# Flyback_Develop.net
KiCad netlist of a schematic drawn in EAGLE
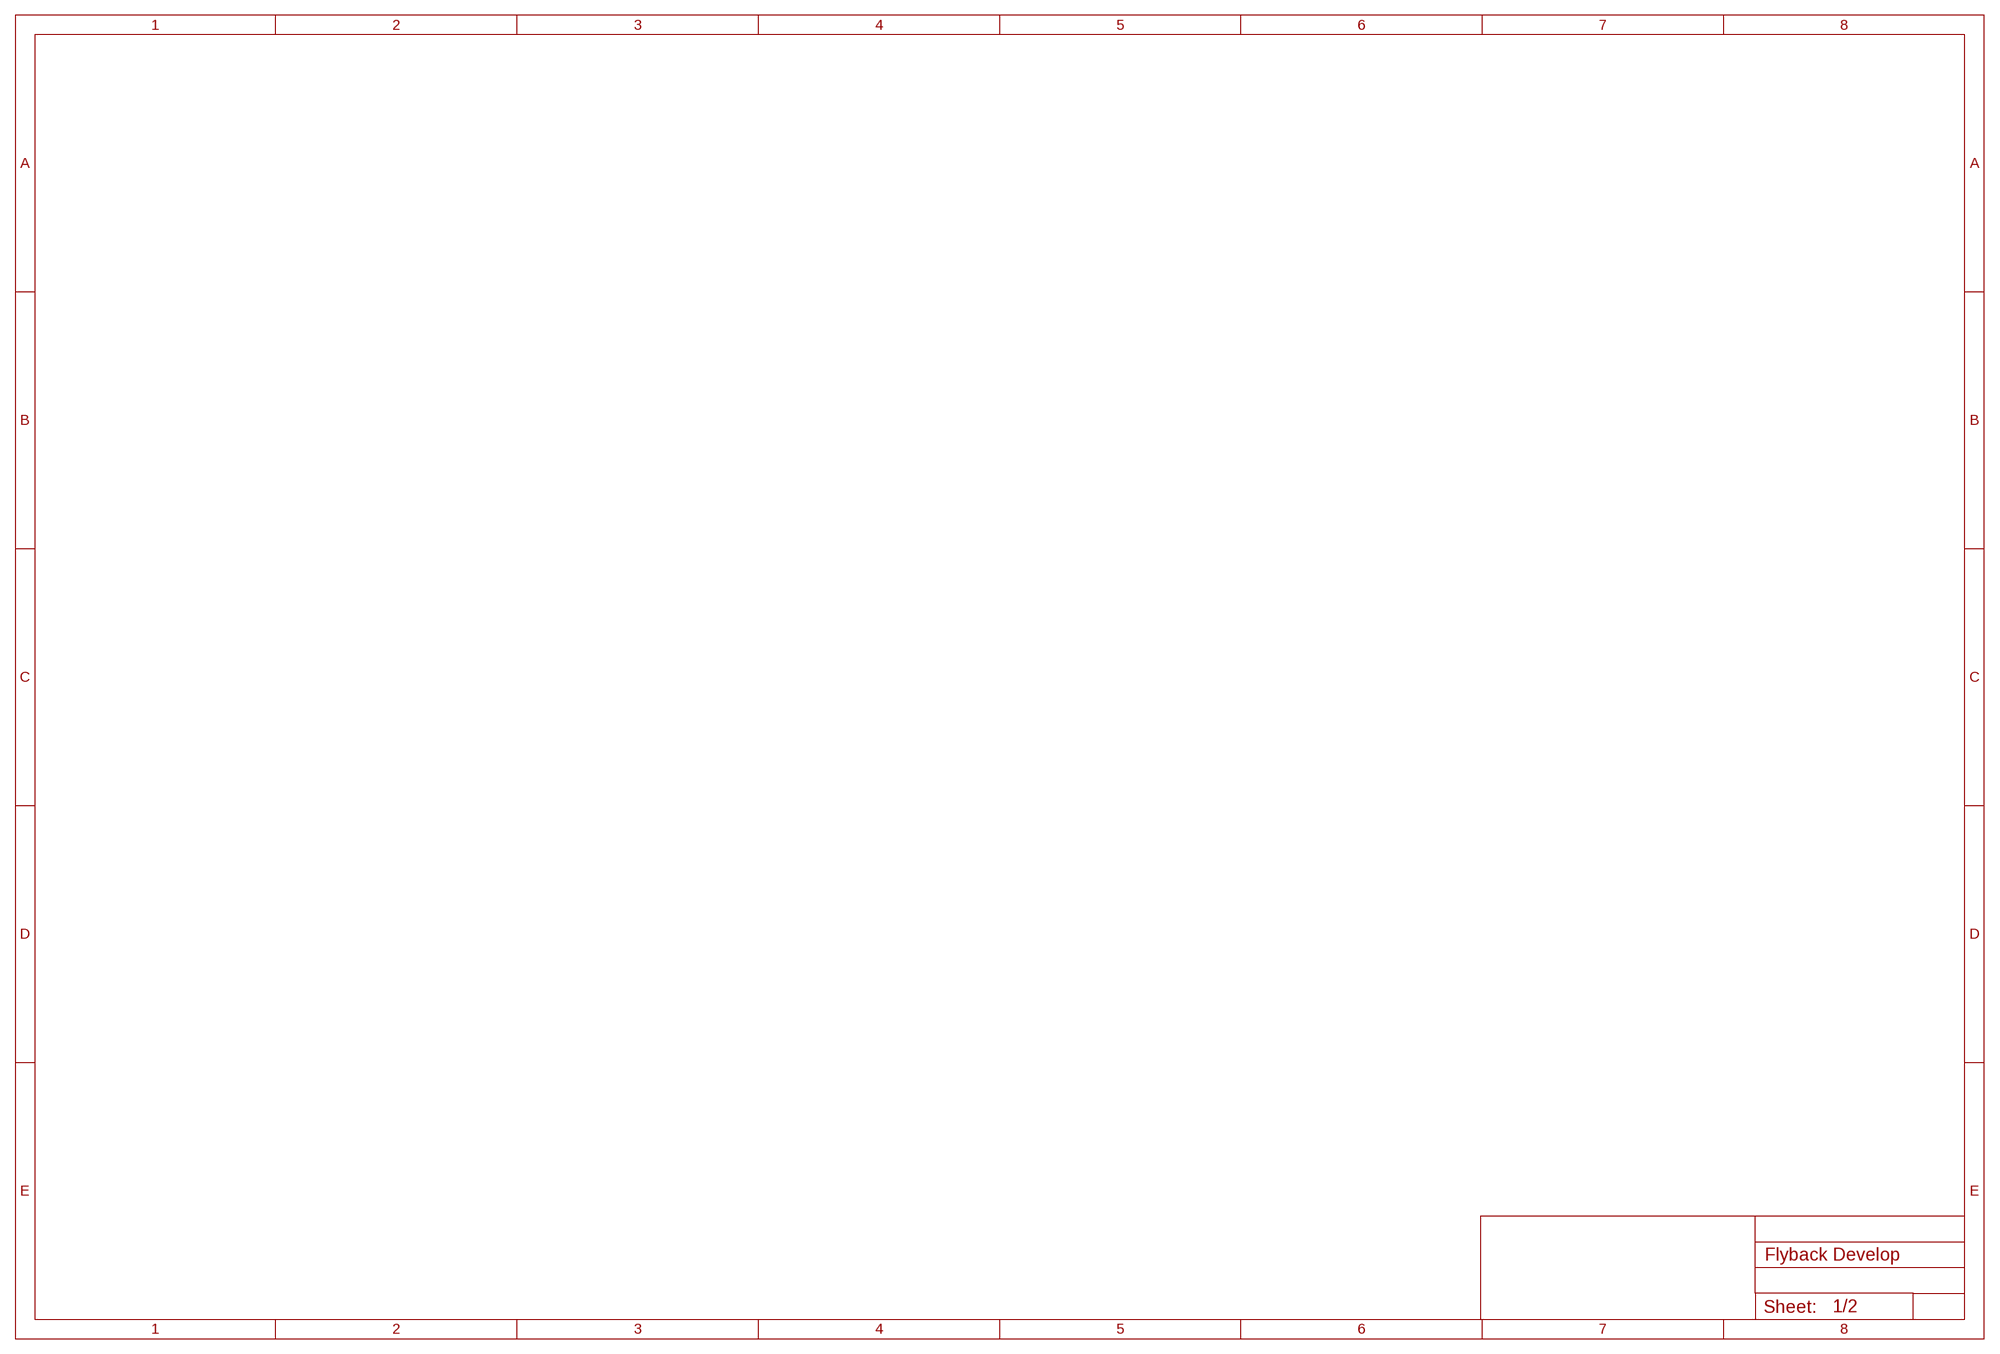
[diagram p0: schematic, sheet 1]
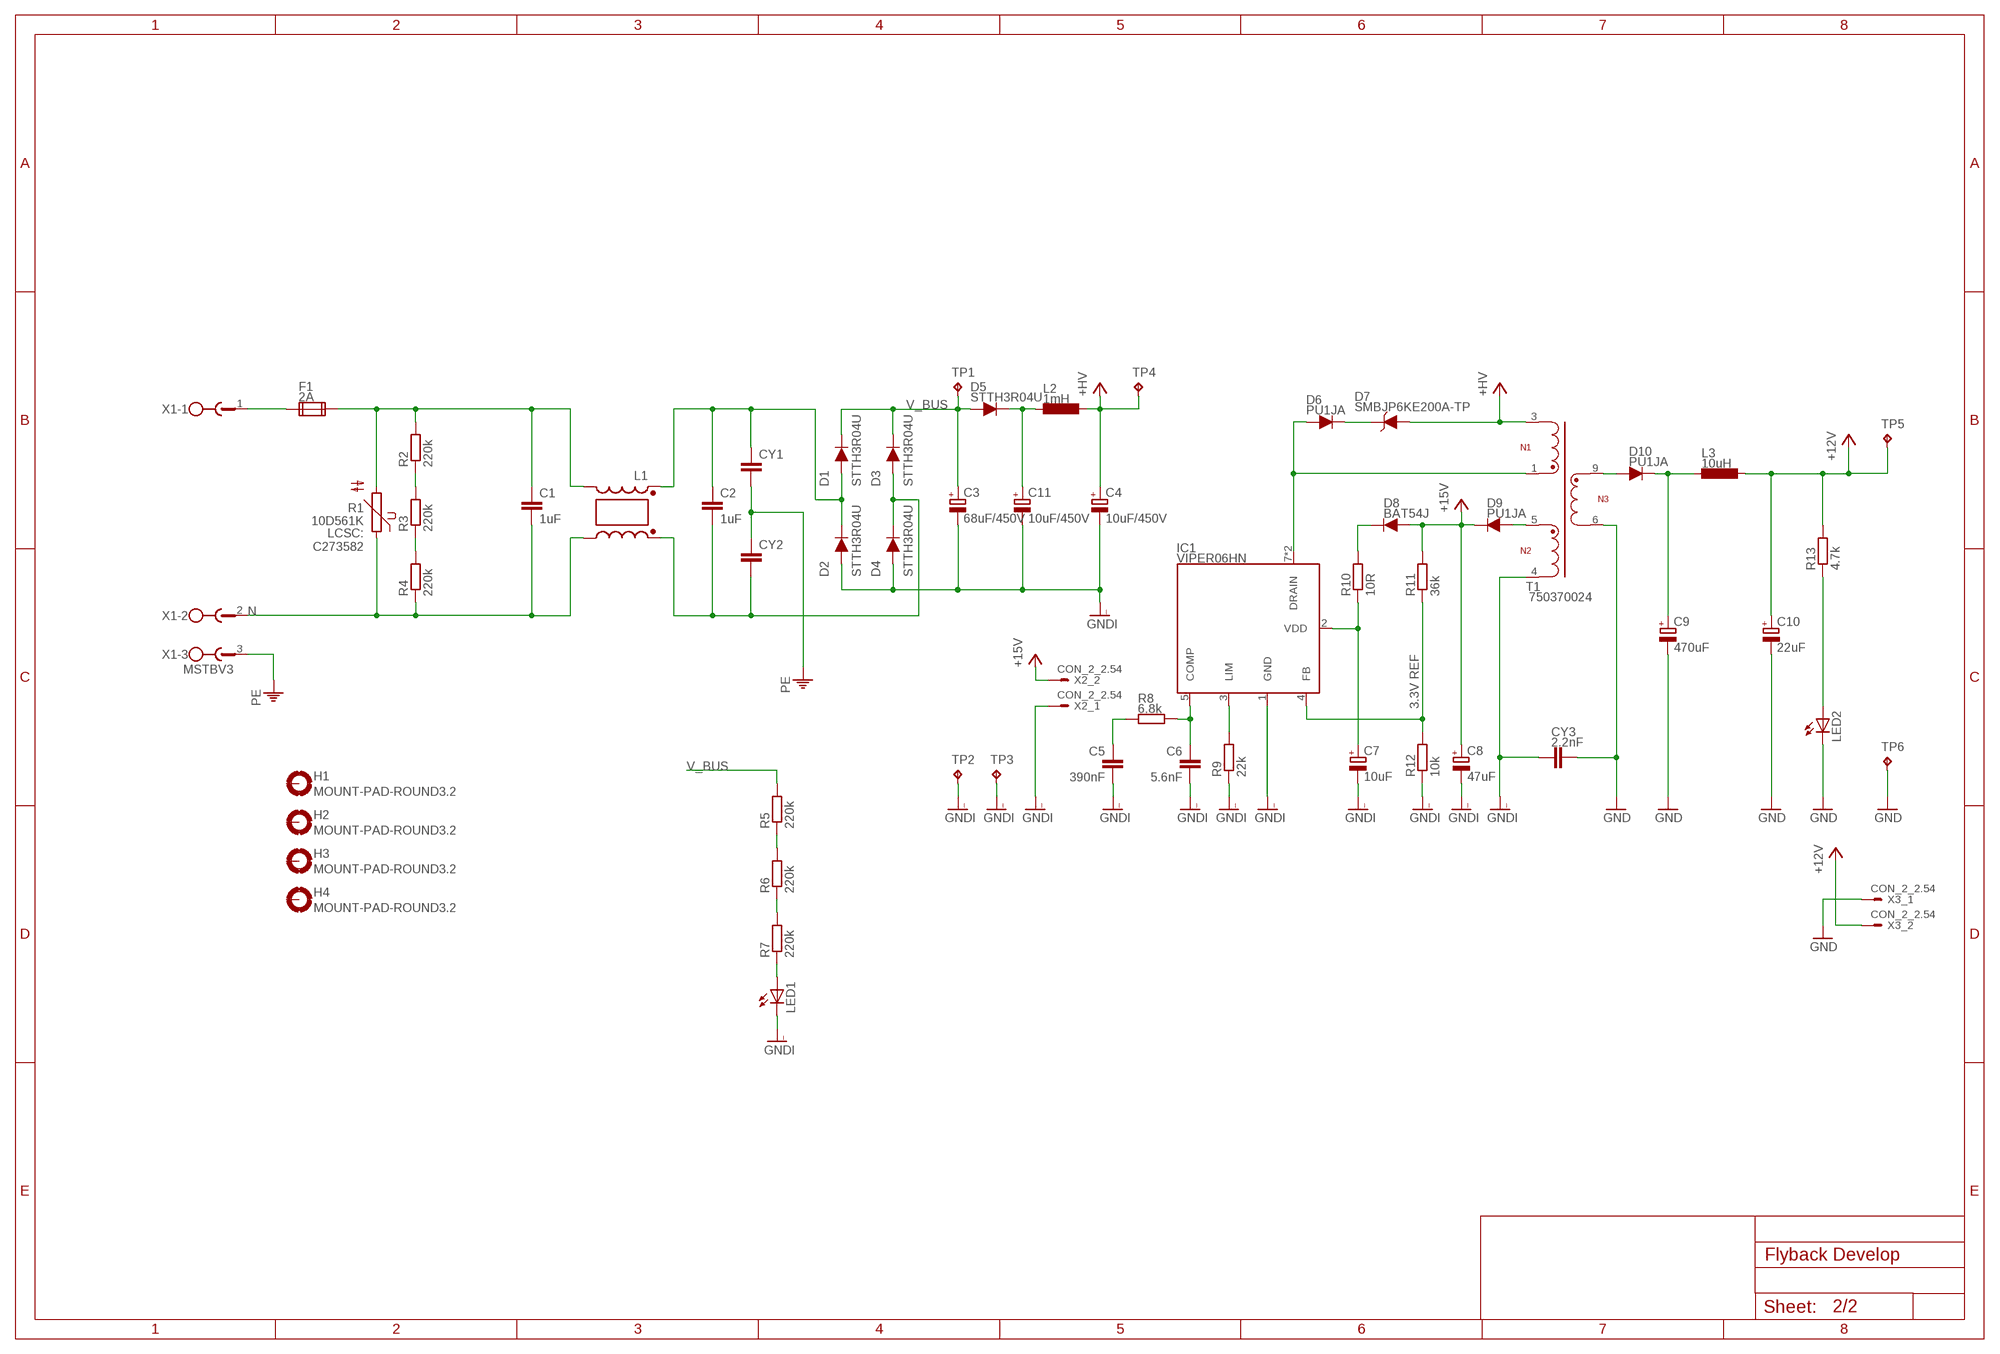
[diagram p1: schematic, sheet 2]

(export (version "E")
  (design (tool "Eeschema 10.0.6"))
  (components
    (comp (ref "C1")
      (value "1uF")
      (footprint "eagle-import:C102-082X133")
      (libsource (lib "eagle-import") (part "C-EU102-082X133"))
    )
    (comp (ref "C2")
      (value "1uF")
      (footprint "eagle-import:C102-082X133")
      (libsource (lib "eagle-import") (part "C-EU102-082X133"))
    )
    (comp (ref "C3")
      (value "68uF/450V")
      (footprint "eagle-import:E7,5-18")
      (libsource (lib "eagle-import") (part "CPOL-EUE7.5-18"))
    )
    (comp (ref "C4")
      (value "10uF/450V")
      (footprint "eagle-import:E3,5-10")
      (libsource (lib "eagle-import") (part "CPOL-EUE3.5-10"))
    )
    (comp (ref "C5")
      (value "390nF")
      (footprint "eagle-import:C0603")
      (libsource (lib "eagle-import") (part "C-EUC0603"))
    )
    (comp (ref "C6")
      (value "5.6nF")
      (footprint "eagle-import:C0603")
      (libsource (lib "eagle-import") (part "C-EUC0603"))
    )
    (comp (ref "C7")
      (value "10uF")
      (footprint "eagle-import:E2,5-5")
      (libsource (lib "eagle-import") (part "CPOL-EUE2.5-5"))
    )
    (comp (ref "C8")
      (value "47uF")
      (footprint "eagle-import:E2,5-7")
      (libsource (lib "eagle-import") (part "CPOL-EUE2.5-7"))
    )
    (comp (ref "C9")
      (value "470uF")
      (footprint "eagle-import:E3,5-8")
      (libsource (lib "eagle-import") (part "CPOL-EUE3.5-8"))
    )
    (comp (ref "C10")
      (value "22uF")
      (footprint "eagle-import:E2-5")
      (libsource (lib "eagle-import") (part "CPOL-EUE2-5"))
    )
    (comp (ref "C11")
      (value "10uF/450V")
      (footprint "eagle-import:E3,5-10")
      (libsource (lib "eagle-import") (part "CPOL-EUE3.5-10"))
    )
    (comp (ref "CY1")
      (value "CYYC7B5")
      (footprint "eagle-import:YC7B5")
      (libsource (lib "eagle-import") (part "CYYC7B5"))
    )
    (comp (ref "CY2")
      (value "CYYC7B5")
      (footprint "eagle-import:YC7B5")
      (libsource (lib "eagle-import") (part "CYYC7B5"))
    )
    (comp (ref "CY3")
      (value "2.2nF")
      (footprint "eagle-import:YC7B5")
      (libsource (lib "eagle-import") (part "CYYC7B5"))
    )
    (comp (ref "D1")
      (value "STTH3R04U")
      (footprint "eagle-import:SMB")
      (libsource (lib "eagle-import") (part "DIODESMB"))
    )
    (comp (ref "D2")
      (value "STTH3R04U")
      (footprint "eagle-import:SMB")
      (libsource (lib "eagle-import") (part "DIODESMB"))
    )
    (comp (ref "D3")
      (value "STTH3R04U")
      (footprint "eagle-import:SMB")
      (libsource (lib "eagle-import") (part "DIODESMB"))
    )
    (comp (ref "D4")
      (value "STTH3R04U")
      (footprint "eagle-import:SMB")
      (libsource (lib "eagle-import") (part "DIODESMB"))
    )
    (comp (ref "D5")
      (value "STTH3R04U")
      (footprint "eagle-import:SMB")
      (libsource (lib "eagle-import") (part "DIODESMB"))
    )
    (comp (ref "D6")
      (value "PU1JA")
      (footprint "eagle-import:DO214AC")
      (libsource (lib "eagle-import") (part "DIODEDO214AC"))
    )
    (comp (ref "D7")
      (value "SMBJP6KE200A-TP")
      (footprint "eagle-import:DO214AC")
      (libsource (lib "eagle-import") (part "TVS_DIODE_UNISMA"))
    )
    (comp (ref "D8")
      (value "BAT54J")
      (footprint "eagle-import:SOD123")
      (libsource (lib "eagle-import") (part "DIODE"))
    )
    (comp (ref "D9")
      (value "PU1JA")
      (footprint "eagle-import:DO214AC")
      (libsource (lib "eagle-import") (part "DIODEDO214AC"))
    )
    (comp (ref "D10")
      (value "PU1JA")
      (footprint "eagle-import:DO214AC")
      (libsource (lib "eagle-import") (part "DIODEDO214AC"))
    )
    (comp (ref "F1")
      (value "2A")
      (footprint "eagle-import:2010-FUSE")
      (libsource (lib "eagle-import") (part "FUSE2010"))
    )
    (comp (ref "H1")
      (value "MOUNT-PAD-ROUND3.2")
      (footprint "eagle-import:3,2-PAD")
      (libsource (lib "eagle-import") (part "MOUNT-PAD-ROUND3.2"))
    )
    (comp (ref "H2")
      (value "MOUNT-PAD-ROUND3.2")
      (footprint "eagle-import:3,2-PAD")
      (libsource (lib "eagle-import") (part "MOUNT-PAD-ROUND3.2"))
    )
    (comp (ref "H3")
      (value "MOUNT-PAD-ROUND3.2")
      (footprint "eagle-import:3,2-PAD")
      (libsource (lib "eagle-import") (part "MOUNT-PAD-ROUND3.2"))
    )
    (comp (ref "H4")
      (value "MOUNT-PAD-ROUND3.2")
      (footprint "eagle-import:3,2-PAD")
      (libsource (lib "eagle-import") (part "MOUNT-PAD-ROUND3.2"))
    )
    (comp (ref "IC1")
      (value "VIPER06HN")
      (footprint "eagle-import:DIL07")
      (libsource (lib "eagle-import") (part "VIPER06HN"))
    )
    (comp (ref "L1")
      (value "20mH")
      (footprint "eagle-import:CMC_SLT")
      (libsource (lib "eagle-import") (part "COMMON_MODE_CHOKE_SLT"))
    )
    (comp (ref "L2")
      (value "1mH")
      (footprint "eagle-import:SLH0704")
      (libsource (lib "eagle-import") (part "COIL_1MH"))
    )
    (comp (ref "L3")
      (value "10uH")
      (footprint "eagle-import:COIL_4X4")
      (libsource (lib "eagle-import") (part "10UH_4X4"))
    )
    (comp (ref "LED1")
      (value "LED_0805")
      (footprint "eagle-import:LED_0805")
      (libsource (lib "eagle-import") (part "LED_0805"))
    )
    (comp (ref "LED2")
      (value "LED_0805")
      (footprint "eagle-import:LED_0805")
      (libsource (lib "eagle-import") (part "LED_0805"))
    )
    (comp (ref "R1")
      (value "10D561K")
      (footprint "eagle-import:S10K175")
      (libsource (lib "eagle-import") (part "S10K175"))
    )
    (comp (ref "R2")
      (value "220k")
      (footprint "eagle-import:R1210")
      (libsource (lib "eagle-import") (part "R-EU_R1210"))
    )
    (comp (ref "R3")
      (value "220k")
      (footprint "eagle-import:R1210")
      (libsource (lib "eagle-import") (part "R-EU_R1210"))
    )
    (comp (ref "R4")
      (value "220k")
      (footprint "eagle-import:R1210")
      (libsource (lib "eagle-import") (part "R-EU_R1210"))
    )
    (comp (ref "R5")
      (value "220k")
      (footprint "eagle-import:R1210")
      (libsource (lib "eagle-import") (part "R-EU_R1210"))
    )
    (comp (ref "R6")
      (value "220k")
      (footprint "eagle-import:R1210")
      (libsource (lib "eagle-import") (part "R-EU_R1210"))
    )
    (comp (ref "R7")
      (value "220k")
      (footprint "eagle-import:R1210")
      (libsource (lib "eagle-import") (part "R-EU_R1210"))
    )
    (comp (ref "R8")
      (value "6.8k")
      (footprint "eagle-import:R0603")
      (libsource (lib "eagle-import") (part "R-EU_R0603"))
    )
    (comp (ref "R9")
      (value "22k")
      (footprint "eagle-import:R0603")
      (libsource (lib "eagle-import") (part "R-EU_R0603"))
    )
    (comp (ref "R10")
      (value "10R")
      (footprint "eagle-import:R0805")
      (libsource (lib "eagle-import") (part "R-EU_R0805"))
    )
    (comp (ref "R11")
      (value "36k")
      (footprint "eagle-import:R0603")
      (libsource (lib "eagle-import") (part "R-EU_R0603"))
    )
    (comp (ref "R12")
      (value "10k")
      (footprint "eagle-import:R0603")
      (libsource (lib "eagle-import") (part "R-EU_R0603"))
    )
    (comp (ref "R13")
      (value "4.7k")
      (footprint "eagle-import:R0603")
      (libsource (lib "eagle-import") (part "R-EU_R0603"))
    )
    (comp (ref "T1")
      (value "750370024")
      (footprint "eagle-import:WE-OLSTM_EE13_L13.72W20.45H10.8")
      (libsource (lib "eagle-import") (part "750370024"))
    )
    (comp (ref "TP1")
      (value "TP_SOLDREYE")
      (footprint "eagle-import:SOLDER_EYE")
      (libsource (lib "eagle-import") (part "TP_SOLDREYE"))
    )
    (comp (ref "TP2")
      (value "TP_SOLDREYE")
      (footprint "eagle-import:SOLDER_EYE")
      (libsource (lib "eagle-import") (part "TP_SOLDREYE"))
    )
    (comp (ref "TP3")
      (value "TP_SOLDREYE")
      (footprint "eagle-import:SOLDER_EYE")
      (libsource (lib "eagle-import") (part "TP_SOLDREYE"))
    )
    (comp (ref "TP4")
      (value "TP_SOLDREYE")
      (footprint "eagle-import:SOLDER_EYE")
      (libsource (lib "eagle-import") (part "TP_SOLDREYE"))
    )
    (comp (ref "TP5")
      (value "TP_SOLDREYE")
      (footprint "eagle-import:SOLDER_EYE")
      (libsource (lib "eagle-import") (part "TP_SOLDREYE"))
    )
    (comp (ref "TP6")
      (value "TP_SOLDREYE")
      (footprint "eagle-import:SOLDER_EYE")
      (libsource (lib "eagle-import") (part "TP_SOLDREYE"))
    )
    (comp (ref "X1")
      (value "MSTBV3")
      (footprint "eagle-import:MSTBV3")
      (fields (field (name "MPN") "MSTBV 2,5/3-GF-5.08"))
      (libsource (lib "eagle-import") (part "MSTBV3"))
    )
    (comp (ref "X2")
      (value "CON_2_2.54")
      (footprint "eagle-import:1X02")
      (libsource (lib "eagle-import") (part "CON_2_2.54"))
    )
    (comp (ref "X3")
      (value "CON_2_2.54")
      (footprint "eagle-import:1X02")
      (libsource (lib "eagle-import") (part "CON_2_2.54"))
    )
  )
  (nets
    (net (code "1") (name "+12V") (class "Default")
      (node (ref "C10") (pin "+") (pinfunction "+_+") (pintype "passive"))
      (node (ref "L3") (pin "1") (pinfunction "1_1") (pintype "passive"))
      (node (ref "R13") (pin "2") (pinfunction "2_2") (pintype "passive"))
      (node (ref "TP5") (pin "1") (pinfunction "TP_1") (pintype "input"))
      (node (ref "X3") (pin "2") (pinfunction "S_2") (pintype "passive"))
    )
    (net (code "2") (name "+15V") (class "Default")
      (node (ref "C8") (pin "+") (pinfunction "+_+") (pintype "passive"))
      (node (ref "D8") (pin "2") (pinfunction "A_2") (pintype "passive"))
      (node (ref "D9") (pin "C") (pinfunction "C_C") (pintype "passive"))
      (node (ref "R11") (pin "2") (pinfunction "2_2") (pintype "passive"))
      (node (ref "X2") (pin "2") (pinfunction "S_2") (pintype "passive"))
    )
    (net (code "3") (name "+HV") (class "Default")
      (node (ref "C4") (pin "+") (pinfunction "+_+") (pintype "passive"))
      (node (ref "D7") (pin "A") (pinfunction "A_A") (pintype "passive"))
      (node (ref "L2") (pin "1") (pinfunction "1_1") (pintype "passive"))
      (node (ref "T1") (pin "3") (pinfunction "3_3") (pintype "passive"))
      (node (ref "TP4") (pin "1") (pinfunction "TP_1") (pintype "input"))
    )
    (net (code "4") (name "GND") (class "Default")
      (node (ref "C10") (pin "-") (pinfunction "-_-") (pintype "passive"))
      (node (ref "C9") (pin "-") (pinfunction "-_-") (pintype "passive"))
      (node (ref "CY3") (pin "2") (pinfunction "2_2") (pintype "passive"))
      (node (ref "LED2") (pin "C") (pinfunction "C_C") (pintype "passive"))
      (node (ref "T1") (pin "6") (pinfunction "6_6") (pintype "passive"))
      (node (ref "TP6") (pin "1") (pinfunction "TP_1") (pintype "input"))
      (node (ref "X3") (pin "1") (pinfunction "S_1") (pintype "passive"))
    )
    (net (code "5") (name "GNDI") (class "Default")
      (node (ref "C11") (pin "-") (pinfunction "-_-") (pintype "passive"))
      (node (ref "C3") (pin "-") (pinfunction "-_-") (pintype "passive"))
      (node (ref "C4") (pin "-") (pinfunction "-_-") (pintype "passive"))
      (node (ref "C5") (pin "2") (pinfunction "2_2") (pintype "passive"))
      (node (ref "C6") (pin "2") (pinfunction "2_2") (pintype "passive"))
      (node (ref "C7") (pin "-") (pinfunction "-_-") (pintype "passive"))
      (node (ref "C8") (pin "-") (pinfunction "-_-") (pintype "passive"))
      (node (ref "CY3") (pin "1") (pinfunction "1_1") (pintype "passive"))
      (node (ref "D2") (pin "A") (pinfunction "A_A") (pintype "passive"))
      (node (ref "D4") (pin "A") (pinfunction "A_A") (pintype "passive"))
      (node (ref "IC1") (pin "1") (pinfunction "GND_1") (pintype "bidirectional"))
      (node (ref "LED1") (pin "C") (pinfunction "C_C") (pintype "passive"))
      (node (ref "R12") (pin "1") (pinfunction "1_1") (pintype "passive"))
      (node (ref "R9") (pin "1") (pinfunction "1_1") (pintype "passive"))
      (node (ref "T1") (pin "4") (pinfunction "4_4") (pintype "passive"))
      (node (ref "TP2") (pin "1") (pinfunction "TP_1") (pintype "input"))
      (node (ref "TP3") (pin "1") (pinfunction "TP_1") (pintype "input"))
      (node (ref "X2") (pin "1") (pinfunction "S_1") (pintype "passive"))
    )
    (net (code "6") (name "N") (class "Default")
      (node (ref "C1") (pin "2") (pinfunction "2_2") (pintype "passive"))
      (node (ref "L1") (pin "OUT2") (pinfunction "OUT2_OUT2") (pintype "passive"))
      (node (ref "R1") (pin "1") (pinfunction "1_1") (pintype "passive"))
      (node (ref "R4") (pin "1") (pinfunction "1_1") (pintype "passive"))
      (node (ref "X1") (pin "2") (pinfunction "1_2") (pintype "passive"))
    )
    (net (code "7") (name "Net-(C2-Pad1)") (class "Default")
      (node (ref "C2") (pin "1") (pinfunction "1_1") (pintype "passive"))
      (node (ref "CY1") (pin "1") (pinfunction "1_1") (pintype "passive"))
      (node (ref "D1") (pin "A") (pinfunction "A_A") (pintype "passive"))
      (node (ref "D2") (pin "C") (pinfunction "C_C") (pintype "passive"))
      (node (ref "L1") (pin "IN1") (pinfunction "IN1_IN1") (pintype "passive"))
    )
    (net (code "8") (name "Net-(C2-Pad2)") (class "Default")
      (node (ref "C2") (pin "2") (pinfunction "2_2") (pintype "passive"))
      (node (ref "CY2") (pin "2") (pinfunction "2_2") (pintype "passive"))
      (node (ref "D3") (pin "A") (pinfunction "A_A") (pintype "passive"))
      (node (ref "D4") (pin "C") (pinfunction "C_C") (pintype "passive"))
      (node (ref "L1") (pin "IN2") (pinfunction "IN2_IN2") (pintype "passive"))
    )
    (net (code "9") (name "Net-(C5-Pad1)") (class "Default")
      (node (ref "C5") (pin "1") (pinfunction "1_1") (pintype "passive"))
      (node (ref "R8") (pin "1") (pinfunction "1_1") (pintype "passive"))
    )
    (net (code "10") (name "Net-(C9-Pad+)") (class "Default")
      (node (ref "C9") (pin "+") (pinfunction "+_+") (pintype "passive"))
      (node (ref "D10") (pin "C") (pinfunction "C_C") (pintype "passive"))
      (node (ref "L3") (pin "2") (pinfunction "2_2") (pintype "passive"))
    )
    (net (code "11") (name "Net-(C11-Pad+)") (class "Default")
      (node (ref "C11") (pin "+") (pinfunction "+_+") (pintype "passive"))
      (node (ref "D5") (pin "C") (pinfunction "C_C") (pintype "passive"))
      (node (ref "L2") (pin "2") (pinfunction "2_2") (pintype "passive"))
    )
    (net (code "12") (name "Net-(D6-PadA)") (class "Default")
      (node (ref "D6") (pin "A") (pinfunction "A_A") (pintype "passive"))
      (node (ref "IC1") (pin "7") (pinfunction "DRAIN_7") (pintype "bidirectional"))
      (node (ref "IC1") (pin "8") (pinfunction "DRAIN_8") (pintype "bidirectional"))
      (node (ref "T1") (pin "1") (pinfunction "1_1") (pintype "passive"))
    )
    (net (code "13") (name "Net-(D6-PadC)") (class "Default")
      (node (ref "D6") (pin "C") (pinfunction "C_C") (pintype "passive"))
      (node (ref "D7") (pin "C") (pinfunction "C_C") (pintype "passive"))
    )
    (net (code "14") (name "Net-(D8-C)") (class "Default")
      (node (ref "D8") (pin "1") (pinfunction "C_1") (pintype "passive"))
      (node (ref "R10") (pin "2") (pinfunction "2_2") (pintype "passive"))
    )
    (net (code "15") (name "Net-(D9-PadA)") (class "Default")
      (node (ref "D9") (pin "A") (pinfunction "A_A") (pintype "passive"))
      (node (ref "T1") (pin "5") (pinfunction "5_5") (pintype "passive"))
    )
    (net (code "16") (name "Net-(D10-PadA)") (class "Default")
      (node (ref "D10") (pin "A") (pinfunction "A_A") (pintype "passive"))
      (node (ref "T1") (pin "9") (pinfunction "9_9") (pintype "passive"))
    )
    (net (code "17") (name "Net-(F1-1)") (class "Default")
      (node (ref "F1") (pin "P$1") (pinfunction "1_P$1") (pintype "passive"))
      (node (ref "X1") (pin "1") (pinfunction "1_1") (pintype "passive"))
    )
    (net (code "18") (name "Net-(F1-2)") (class "Default")
      (node (ref "C1") (pin "1") (pinfunction "1_1") (pintype "passive"))
      (node (ref "F1") (pin "P$2") (pinfunction "2_P$2") (pintype "passive"))
      (node (ref "L1") (pin "OUT1") (pinfunction "OUT1_OUT1") (pintype "passive"))
      (node (ref "R1") (pin "2") (pinfunction "2_2") (pintype "passive"))
      (node (ref "R2") (pin "2") (pinfunction "2_2") (pintype "passive"))
    )
    (net (code "19") (name "Net-(IC1-COMP)") (class "Default")
      (node (ref "C6") (pin "1") (pinfunction "1_1") (pintype "passive"))
      (node (ref "IC1") (pin "5") (pinfunction "COMP_5") (pintype "bidirectional"))
      (node (ref "R8") (pin "2") (pinfunction "2_2") (pintype "passive"))
    )
    (net (code "20") (name "Net-(IC1-FB)") (class "Default")
      (node (ref "IC1") (pin "4") (pinfunction "FB_4") (pintype "bidirectional"))
      (node (ref "R11") (pin "1") (pinfunction "1_1") (pintype "passive"))
      (node (ref "R12") (pin "2") (pinfunction "2_2") (pintype "passive"))
    )
    (net (code "21") (name "Net-(IC1-LIM)") (class "Default")
      (node (ref "IC1") (pin "3") (pinfunction "LIM_3") (pintype "bidirectional"))
      (node (ref "R9") (pin "2") (pinfunction "2_2") (pintype "passive"))
    )
    (net (code "22") (name "Net-(IC1-VDD)") (class "Default")
      (node (ref "C7") (pin "+") (pinfunction "+_+") (pintype "passive"))
      (node (ref "IC1") (pin "2") (pinfunction "VDD_2") (pintype "bidirectional"))
      (node (ref "R10") (pin "1") (pinfunction "1_1") (pintype "passive"))
    )
    (net (code "23") (name "Net-(LED1-PadA)") (class "Default")
      (node (ref "LED1") (pin "A") (pinfunction "A_A") (pintype "passive"))
      (node (ref "R7") (pin "1") (pinfunction "1_1") (pintype "passive"))
    )
    (net (code "24") (name "Net-(LED2-PadA)") (class "Default")
      (node (ref "LED2") (pin "A") (pinfunction "A_A") (pintype "passive"))
      (node (ref "R13") (pin "1") (pinfunction "1_1") (pintype "passive"))
    )
    (net (code "25") (name "Net-(R2-Pad1)") (class "Default")
      (node (ref "R2") (pin "1") (pinfunction "1_1") (pintype "passive"))
      (node (ref "R3") (pin "2") (pinfunction "2_2") (pintype "passive"))
    )
    (net (code "26") (name "Net-(R3-Pad1)") (class "Default")
      (node (ref "R3") (pin "1") (pinfunction "1_1") (pintype "passive"))
      (node (ref "R4") (pin "2") (pinfunction "2_2") (pintype "passive"))
    )
    (net (code "27") (name "Net-(R5-Pad1)") (class "Default")
      (node (ref "R5") (pin "1") (pinfunction "1_1") (pintype "passive"))
      (node (ref "R6") (pin "2") (pinfunction "2_2") (pintype "passive"))
    )
    (net (code "28") (name "Net-(R6-Pad1)") (class "Default")
      (node (ref "R6") (pin "1") (pinfunction "1_1") (pintype "passive"))
      (node (ref "R7") (pin "2") (pinfunction "2_2") (pintype "passive"))
    )
    (net (code "29") (name "PE") (class "Default")
      (node (ref "CY1") (pin "2") (pinfunction "2_2") (pintype "passive"))
      (node (ref "CY2") (pin "1") (pinfunction "1_1") (pintype "passive"))
      (node (ref "X1") (pin "3") (pinfunction "1_3") (pintype "passive"))
    )
    (net (code "30") (name "V_BUS") (class "Default")
      (node (ref "C3") (pin "+") (pinfunction "+_+") (pintype "passive"))
      (node (ref "D1") (pin "C") (pinfunction "C_C") (pintype "passive"))
      (node (ref "D3") (pin "C") (pinfunction "C_C") (pintype "passive"))
      (node (ref "D5") (pin "A") (pinfunction "A_A") (pintype "passive"))
      (node (ref "R5") (pin "2") (pinfunction "2_2") (pintype "passive"))
      (node (ref "TP1") (pin "1") (pinfunction "TP_1") (pintype "input"))
    )
    (net (code "31") (name "unconnected-(H1-MOUNT-PadB3,2)") (class "Default")
      (node (ref "H1") (pin "B3,2") (pinfunction "MOUNT_B3,2") (pintype "passive"))
    )
    (net (code "32") (name "unconnected-(H2-MOUNT-PadB3,2)") (class "Default")
      (node (ref "H2") (pin "B3,2") (pinfunction "MOUNT_B3,2") (pintype "passive"))
    )
    (net (code "33") (name "unconnected-(H3-MOUNT-PadB3,2)") (class "Default")
      (node (ref "H3") (pin "B3,2") (pinfunction "MOUNT_B3,2") (pintype "passive"))
    )
    (net (code "34") (name "unconnected-(H4-MOUNT-PadB3,2)") (class "Default")
      (node (ref "H4") (pin "B3,2") (pinfunction "MOUNT_B3,2") (pintype "passive"))
    )
  )
)
